# controller_board.net
KiCad netlist of a schematic drawn in EAGLE
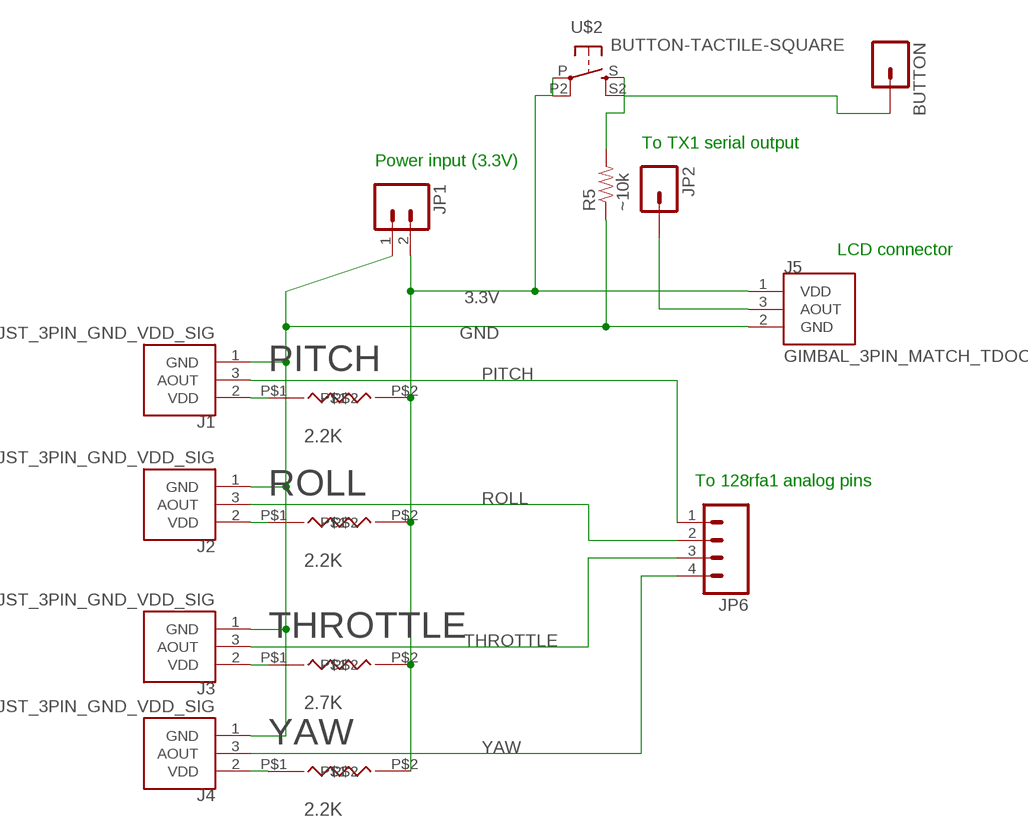
[diagram p0: schematic, sheet 1]

(export (version "E")
  (design (tool "Eeschema 10.0.6"))
  (components
    (comp (ref "BUTTON")
      (value "M01PTH")
      (footprint "eagle-import:1X01")
      (libsource (lib "eagle-import") (part "M01PTH"))
    )
    (comp (ref "J1")
      (value "JST_3PIN_GND_VDD_SIG")
      (footprint "eagle-import:JST-3-PTH-REVERSE")
      (libsource (lib "eagle-import") (part "JST_3PIN_GND_VDD_SIG"))
    )
    (comp (ref "J2")
      (value "JST_3PIN_GND_VDD_SIG")
      (footprint "eagle-import:JST-3-PTH-REVERSE")
      (libsource (lib "eagle-import") (part "JST_3PIN_GND_VDD_SIG"))
    )
    (comp (ref "J3")
      (value "JST_3PIN_GND_VDD_SIG")
      (footprint "eagle-import:JST-3-PTH-REVERSE")
      (libsource (lib "eagle-import") (part "JST_3PIN_GND_VDD_SIG"))
    )
    (comp (ref "J4")
      (value "JST_3PIN_GND_VDD_SIG")
      (footprint "eagle-import:JST-3-PTH-REVERSE")
      (libsource (lib "eagle-import") (part "JST_3PIN_GND_VDD_SIG"))
    )
    (comp (ref "J5")
      (value "GIMBAL_3PIN_MATCH_TDOCU")
      (footprint "eagle-import:JST-3-PTH")
      (libsource (lib "eagle-import") (part "GIMBAL_3PIN_MATCH_TDOCU"))
    )
    (comp (ref "JP1")
      (value "M021X02_NO_SILK")
      (footprint "eagle-import:1X02_NO_SILK")
      (libsource (lib "eagle-import") (part "M021X02_NO_SILK"))
    )
    (comp (ref "JP2")
      (value "M01PTH")
      (footprint "eagle-import:1X01")
      (libsource (lib "eagle-import") (part "M01PTH"))
    )
    (comp (ref "JP6")
      (value "M04PTH")
      (footprint "eagle-import:1X04")
      (libsource (lib "eagle-import") (part "M04PTH"))
    )
    (comp (ref "PITCH")
      (value "2.2K")
      (footprint "eagle-import:RESISTOR_THROUGH_HOLE")
      (fields (field (name "CREATOR") "Kirt Spotkaeff"))
      (libsource (lib "eagle-import") (part "RESISTOR_THROUGH_HOLE"))
    )
    (comp (ref "R5")
      (value "~10k")
      (footprint "eagle-import:AXIAL-0.4")
      (libsource (lib "eagle-import") (part "RESISTORPTH-1/4W"))
    )
    (comp (ref "ROLL")
      (value "2.2K")
      (footprint "eagle-import:RESISTOR_THROUGH_HOLE")
      (fields (field (name "CREATOR") "Kirt Spotkaeff"))
      (libsource (lib "eagle-import") (part "RESISTOR_THROUGH_HOLE"))
    )
    (comp (ref "THROTTLE")
      (value "2.7K")
      (footprint "eagle-import:RESISTOR_THROUGH_HOLE")
      (fields (field (name "CREATOR") "Kirt Spotkaeff"))
      (libsource (lib "eagle-import") (part "RESISTOR_THROUGH_HOLE"))
    )
    (comp (ref "U$2")
      (value "BUTTON-TACTILE-SQUARE")
      (footprint "eagle-import:BUTTON-TACTILE-SQUARE-ADAFRUIT1010")
      (libsource (lib "eagle-import") (part "BUTTON-TACTILE-SQUARE"))
    )
    (comp (ref "YAW")
      (value "2.2K")
      (footprint "eagle-import:RESISTOR_THROUGH_HOLE")
      (fields (field (name "CREATOR") "Kirt Spotkaeff"))
      (libsource (lib "eagle-import") (part "RESISTOR_THROUGH_HOLE"))
    )
  )
  (nets
    (net (code "1") (name "/3.3V") (class "Default")
      (node (ref "J5") (pin "1") (pinfunction "VDD_1") (pintype "power_in"))
      (node (ref "JP1") (pin "2") (pinfunction "2_2") (pintype "passive"))
      (node (ref "PITCH") (pin "P$2") (pinfunction "P$2_P$2") (pintype "bidirectional"))
      (node (ref "ROLL") (pin "P$2") (pinfunction "P$2_P$2") (pintype "bidirectional"))
      (node (ref "THROTTLE") (pin "P$2") (pinfunction "P$2_P$2") (pintype "bidirectional"))
      (node (ref "U$2") (pin "P") (pinfunction "P_P") (pintype "passive"))
      (node (ref "U$2") (pin "P2") (pinfunction "P1_P2") (pintype "passive"))
      (node (ref "YAW") (pin "P$2") (pinfunction "P$2_P$2") (pintype "bidirectional"))
    )
    (net (code "2") (name "/GND") (class "Default")
      (node (ref "J1") (pin "1") (pinfunction "GND_1") (pintype "power_in"))
      (node (ref "J2") (pin "1") (pinfunction "GND_1") (pintype "power_in"))
      (node (ref "J3") (pin "1") (pinfunction "GND_1") (pintype "power_in"))
      (node (ref "J4") (pin "1") (pinfunction "GND_1") (pintype "power_in"))
      (node (ref "J5") (pin "2") (pinfunction "GND_2") (pintype "power_in"))
      (node (ref "JP1") (pin "1") (pinfunction "1_1") (pintype "passive"))
      (node (ref "R5") (pin "P$1") (pinfunction "1_P$1") (pintype "passive"))
    )
    (net (code "3") (name "/PITCH") (class "Default")
      (node (ref "J1") (pin "3") (pinfunction "AOUT_3") (pintype "bidirectional"))
      (node (ref "JP6") (pin "1") (pinfunction "1_1") (pintype "passive"))
    )
    (net (code "4") (name "/ROLL") (class "Default")
      (node (ref "J2") (pin "3") (pinfunction "AOUT_3") (pintype "bidirectional"))
      (node (ref "JP6") (pin "2") (pinfunction "2_2") (pintype "passive"))
    )
    (net (code "5") (name "/THROTTLE") (class "Default")
      (node (ref "J3") (pin "3") (pinfunction "AOUT_3") (pintype "bidirectional"))
      (node (ref "JP6") (pin "3") (pinfunction "3_3") (pintype "passive"))
    )
    (net (code "6") (name "/YAW") (class "Default")
      (node (ref "J4") (pin "3") (pinfunction "AOUT_3") (pintype "bidirectional"))
      (node (ref "JP6") (pin "4") (pinfunction "4_4") (pintype "passive"))
    )
    (net (code "7") (name "Net-(J1-VDD)") (class "Default")
      (node (ref "J1") (pin "2") (pinfunction "VDD_2") (pintype "power_in"))
      (node (ref "PITCH") (pin "P$1") (pinfunction "P$1_P$1") (pintype "bidirectional"))
    )
    (net (code "8") (name "Net-(J2-VDD)") (class "Default")
      (node (ref "J2") (pin "2") (pinfunction "VDD_2") (pintype "power_in"))
      (node (ref "ROLL") (pin "P$1") (pinfunction "P$1_P$1") (pintype "bidirectional"))
    )
    (net (code "9") (name "Net-(J3-VDD)") (class "Default")
      (node (ref "J3") (pin "2") (pinfunction "VDD_2") (pintype "power_in"))
      (node (ref "THROTTLE") (pin "P$1") (pinfunction "P$1_P$1") (pintype "bidirectional"))
    )
    (net (code "10") (name "Net-(J4-VDD)") (class "Default")
      (node (ref "J4") (pin "2") (pinfunction "VDD_2") (pintype "power_in"))
      (node (ref "YAW") (pin "P$1") (pinfunction "P$1_P$1") (pintype "bidirectional"))
    )
    (net (code "11") (name "Net-(J5-AOUT)") (class "Default")
      (node (ref "J5") (pin "3") (pinfunction "AOUT_3") (pintype "bidirectional"))
      (node (ref "JP2") (pin "1") (pinfunction "1_1") (pintype "passive"))
    )
    (net (code "12") (name "Net-(R5-2)") (class "Default")
      (node (ref "BUTTON") (pin "1") (pinfunction "1_1") (pintype "passive"))
      (node (ref "R5") (pin "P$2") (pinfunction "2_P$2") (pintype "passive"))
      (node (ref "U$2") (pin "S") (pinfunction "S_S") (pintype "passive"))
      (node (ref "U$2") (pin "S2") (pinfunction "S1_S2") (pintype "passive"))
    )
  )
)
